# design.net
KiCad netlist of a schematic drawn in Altium Designer
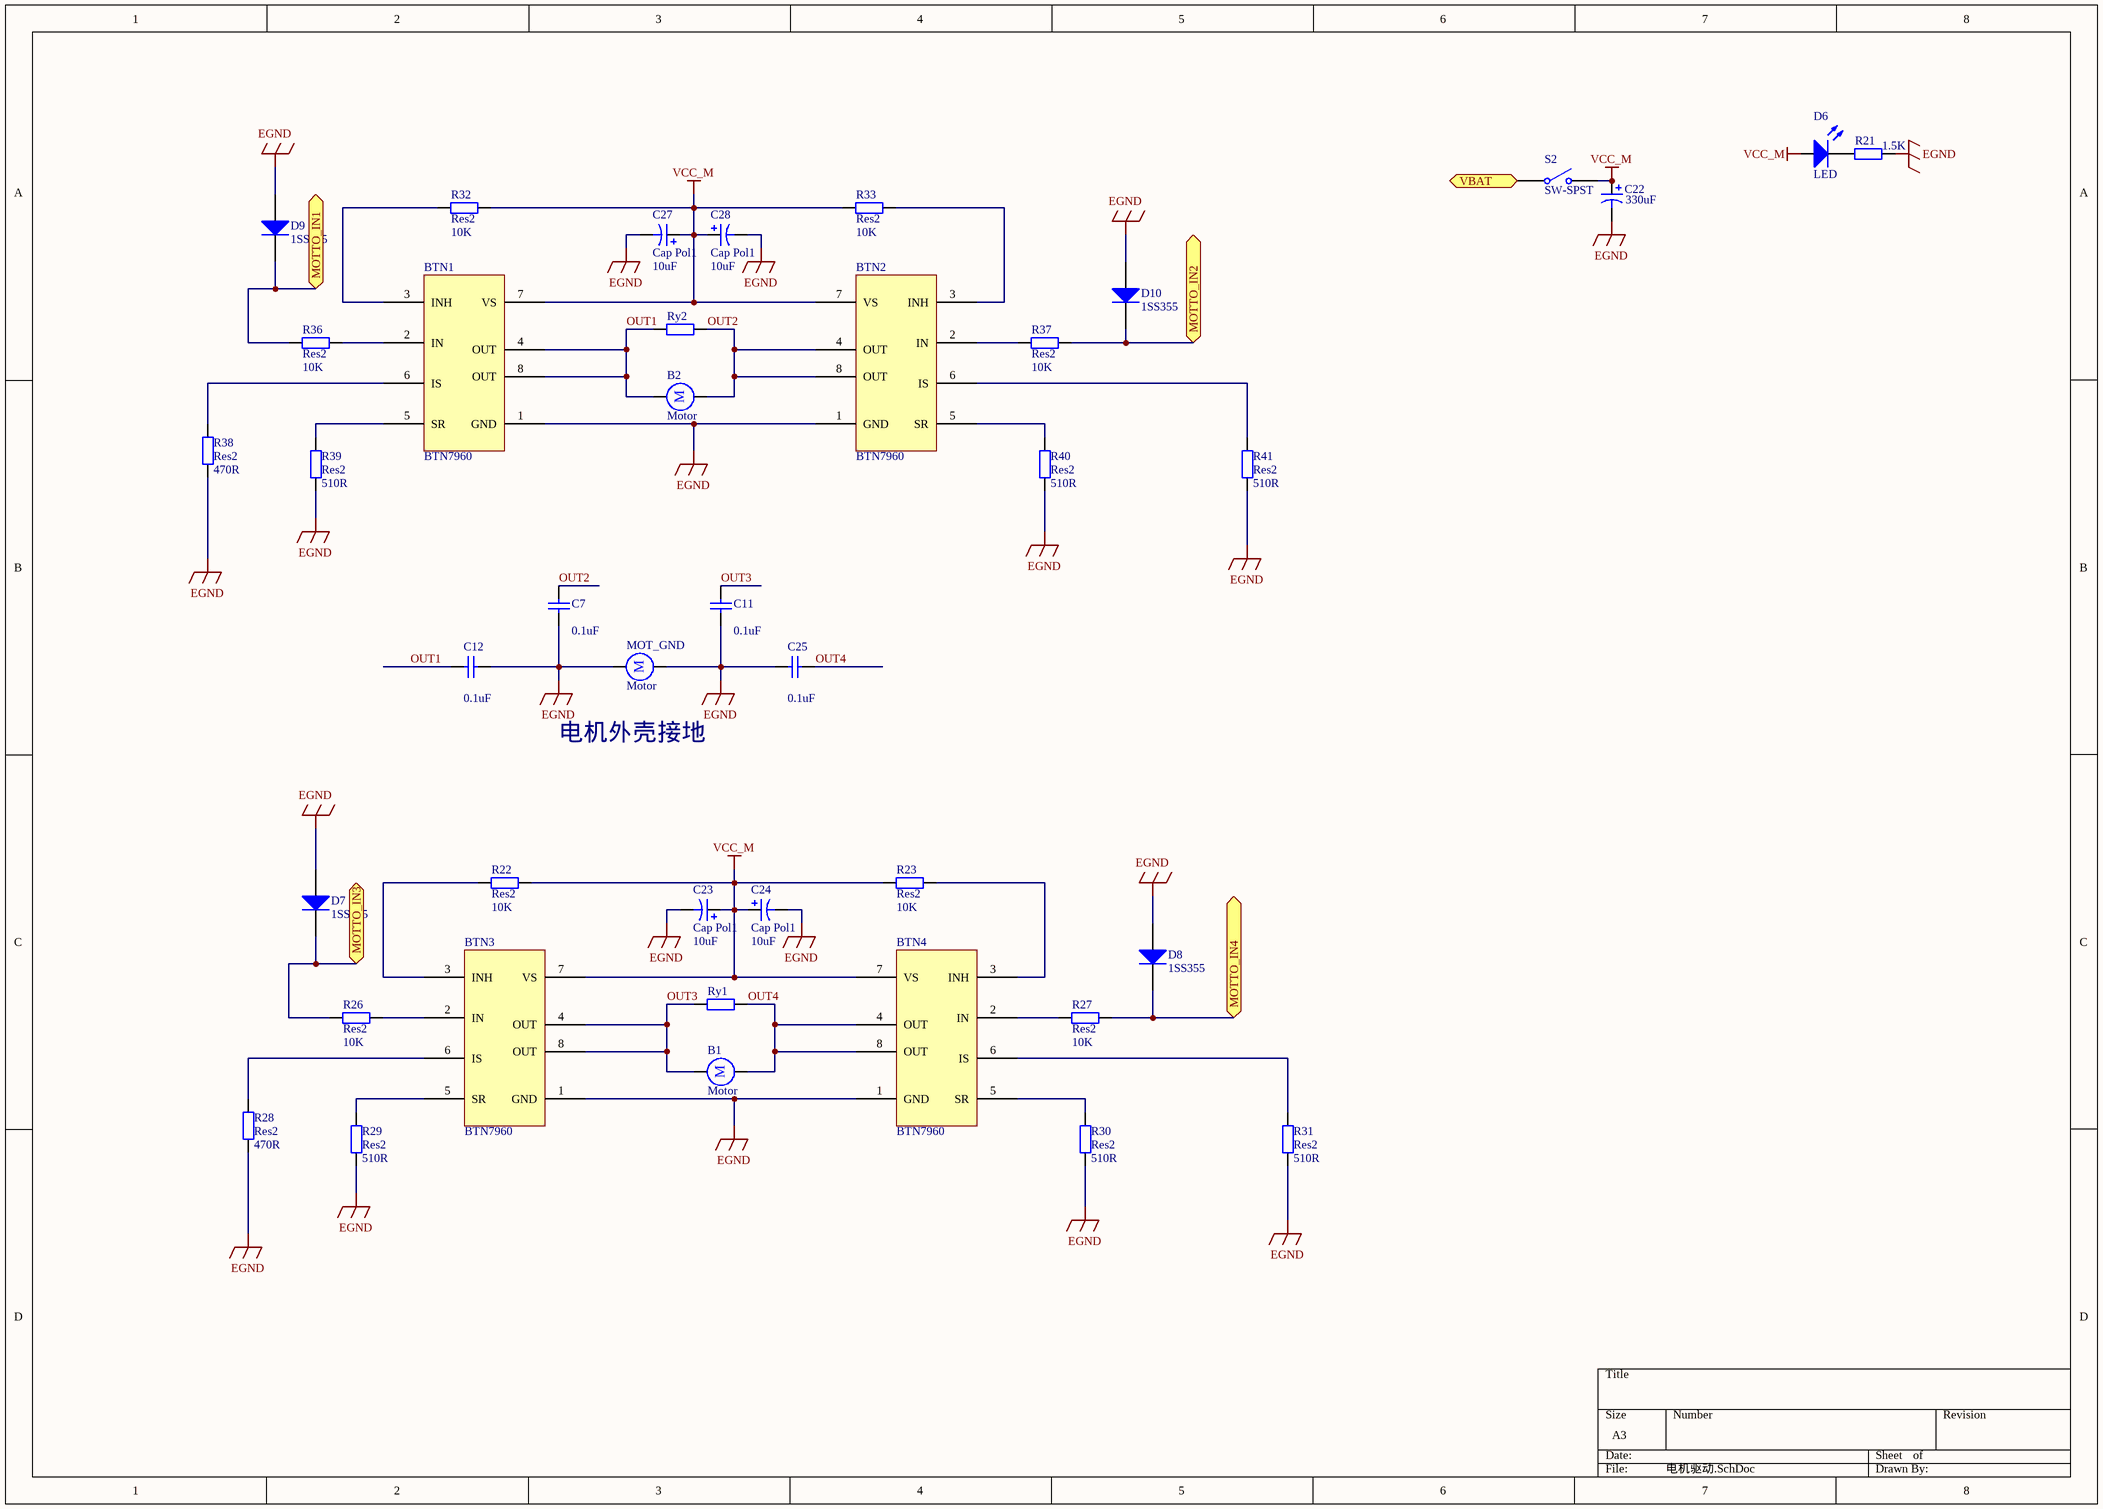
[diagram p0: 电机驱动.SchDoc]

(export (version "E")
  (design (tool "Eeschema 10.0.6"))
  (components
    (comp (ref "B1")
      (value "Motor")
      (footprint "KF301-2P")
      (description "Motor, General Kind")
      (libsource (lib "Landzo") (part "Motor"))
    )
    (comp (ref "B2")
      (value "Motor")
      (footprint "KF301-2P")
      (description "Motor, General Kind")
      (libsource (lib "Landzo") (part "Motor"))
    )
    (comp (ref "BTN1") (value "BTN7960") (footprint "PG-TO263-7-1") (libsource (lib "") (part "BTN7960_1")))
    (comp (ref "BTN2")
      (value "BTN7960")
      (footprint "PG-TO263-7-1")
      (libsource (lib "Landzo") (part "BTN7960"))
    )
    (comp (ref "BTN3") (value "BTN7960") (footprint "PG-TO263-7-1") (libsource (lib "") (part "BTN7960_1")))
    (comp (ref "BTN4")
      (value "BTN7960")
      (footprint "PG-TO263-7-1")
      (libsource (lib "Landzo") (part "BTN7960"))
    )
    (comp (ref "C7")
      (value "0.1uF")
      (footprint "C2012")
      (description "Capacitor")
      (fields (field (name "Comment") "Cap") (field (name "PUBLISHER") "Altium Limited"))
      (libsource (lib "Miscellaneous Devices") (part "Cap"))
    )
    (comp (ref "C11")
      (value "0.1uF")
      (footprint "C2012")
      (description "Capacitor")
      (fields (field (name "Comment") "Cap") (field (name "PUBLISHER") "Altium Limited"))
      (libsource (lib "Miscellaneous Devices") (part "Cap"))
    )
    (comp (ref "C12")
      (value "0.1uF")
      (footprint "C2012")
      (description "Capacitor")
      (fields (field (name "Comment") "Cap") (field (name "PUBLISHER") "Altium Limited"))
      (libsource (lib "Miscellaneous Devices") (part "Cap"))
    )
    (comp (ref "C22")
      (value "330uF")
      (footprint "SMD-EC-F8")
      (description "Polarized Capacitor (Radial)")
      (fields (field (name "Comment") "Cap Pol1") (field (name "PUBLISHER") "Altium Limited"))
      (libsource (lib "Miscellaneous Devices") (part "Cap Pol1"))
    )
    (comp (ref "C23")
      (value "Cap Pol1")
      (footprint "1206(2)")
      (description "Polarized Capacitor (Radial)")
      (fields (field (name "ALTIUM_VALUE") "10uF") (field (name "PUBLISHER") "Altium Limited"))
      (libsource (lib "Miscellaneous Devices") (part "Cap Pol1"))
    )
    (comp (ref "C24")
      (value "Cap Pol1")
      (footprint "1206(2)")
      (description "Polarized Capacitor (Radial)")
      (fields (field (name "ALTIUM_VALUE") "10uF") (field (name "PUBLISHER") "Altium Limited"))
      (libsource (lib "Miscellaneous Devices") (part "Cap Pol1"))
    )
    (comp (ref "C25")
      (value "0.1uF")
      (footprint "C2012")
      (description "Capacitor")
      (fields (field (name "Comment") "Cap") (field (name "PUBLISHER") "Altium Limited"))
      (libsource (lib "Miscellaneous Devices") (part "Cap"))
    )
    (comp (ref "C27")
      (value "Cap Pol1")
      (footprint "1206(2)")
      (description "Polarized Capacitor (Radial)")
      (fields (field (name "ALTIUM_VALUE") "10uF") (field (name "PUBLISHER") "Altium Limited"))
      (libsource (lib "Miscellaneous Devices") (part "Cap Pol1"))
    )
    (comp (ref "C28")
      (value "Cap Pol1")
      (footprint "1206(2)")
      (description "Polarized Capacitor (Radial)")
      (fields (field (name "ALTIUM_VALUE") "10uF") (field (name "PUBLISHER") "Altium Limited"))
      (libsource (lib "Miscellaneous Devices") (part "Cap Pol1"))
    )
    (comp (ref "D6")
      (value "LED")
      (footprint "C2012")
      (description "Typical INFRARED GaAs LED")
      (libsource (lib "Landzo") (part "LED"))
    )
    (comp (ref "D7")
      (value "1SS355")
      (footprint "1206(2)")
      (description "High Conductance Fast Diode")
      (fields (field (name "PUBLISHER") "Altium Limited"))
      (libsource (lib "K60-V4.0") (part "Diode 1N4148"))
    )
    (comp (ref "D8")
      (value "1SS355")
      (footprint "1206(2)")
      (description "High Conductance Fast Diode")
      (fields (field (name "PUBLISHER") "Altium Limited"))
      (libsource (lib "K60-V4.0") (part "Diode 1N4148"))
    )
    (comp (ref "D9")
      (value "1SS355")
      (footprint "1206(2)")
      (description "High Conductance Fast Diode")
      (fields (field (name "PUBLISHER") "Altium Limited"))
      (libsource (lib "K60-V4.0") (part "Diode 1N4148"))
    )
    (comp (ref "D10")
      (value "1SS355")
      (footprint "1206(2)")
      (description "High Conductance Fast Diode")
      (fields (field (name "PUBLISHER") "Altium Limited"))
      (libsource (lib "K60-V4.0") (part "Diode 1N4148"))
    )
    (comp (ref "MOT_GND")
      (value "Motor")
      (footprint "KF301-2P")
      (description "Motor, General Kind")
      (libsource (lib "Landzo") (part "Motor"))
    )
    (comp (ref "R21")
      (value "1.5K")
      (footprint "R2012")
      (description "Resistor")
      (fields (field (name "Comment") "Res2") (field (name "PUBLISHER") "Altium Limited"))
      (libsource (lib "Miscellaneous Devices") (part "Res2"))
    )
    (comp (ref "R22")
      (value "Res2")
      (footprint "R2012")
      (description "Resistor")
      (fields (field (name "ALTIUM_VALUE") "10K") (field (name "PUBLISHER") "Altium Limited"))
      (libsource (lib "") (part "Res2_1"))
    )
    (comp (ref "R23")
      (value "Res2")
      (footprint "R2012")
      (description "Resistor")
      (fields (field (name "ALTIUM_VALUE") "10K") (field (name "PUBLISHER") "Altium Limited"))
      (libsource (lib "") (part "Res2_1"))
    )
    (comp (ref "R26")
      (value "Res2")
      (footprint "R2012")
      (description "Resistor")
      (fields (field (name "ALTIUM_VALUE") "10K") (field (name "PUBLISHER") "Altium Limited"))
      (libsource (lib "") (part "Res2_1"))
    )
    (comp (ref "R27")
      (value "Res2")
      (footprint "R2012")
      (description "Resistor")
      (fields (field (name "ALTIUM_VALUE") "10K") (field (name "PUBLISHER") "Altium Limited"))
      (libsource (lib "") (part "Res2_1"))
    )
    (comp (ref "R28")
      (value "Res2")
      (footprint "R2012")
      (description "Resistor")
      (fields (field (name "ALTIUM_VALUE") "470R") (field (name "PUBLISHER") "Altium Limited"))
      (libsource (lib "") (part "Res2_2"))
    )
    (comp (ref "R29")
      (value "Res2")
      (footprint "R2012")
      (description "Resistor")
      (fields (field (name "ALTIUM_VALUE") "510R") (field (name "PUBLISHER") "Altium Limited"))
      (libsource (lib "") (part "Res2_2"))
    )
    (comp (ref "R30")
      (value "Res2")
      (footprint "R2012")
      (description "Resistor")
      (fields (field (name "ALTIUM_VALUE") "510R") (field (name "PUBLISHER") "Altium Limited"))
      (libsource (lib "") (part "Res2_2"))
    )
    (comp (ref "R31")
      (value "Res2")
      (footprint "R2012")
      (description "Resistor")
      (fields (field (name "ALTIUM_VALUE") "510R") (field (name "PUBLISHER") "Altium Limited"))
      (libsource (lib "") (part "Res2_2"))
    )
    (comp (ref "R32")
      (value "Res2")
      (footprint "R2012")
      (description "Resistor")
      (fields (field (name "ALTIUM_VALUE") "10K") (field (name "PUBLISHER") "Altium Limited"))
      (libsource (lib "") (part "Res2_1"))
    )
    (comp (ref "R33")
      (value "Res2")
      (footprint "R2012")
      (description "Resistor")
      (fields (field (name "ALTIUM_VALUE") "10K") (field (name "PUBLISHER") "Altium Limited"))
      (libsource (lib "") (part "Res2_1"))
    )
    (comp (ref "R36")
      (value "Res2")
      (footprint "R2012")
      (description "Resistor")
      (fields (field (name "ALTIUM_VALUE") "10K") (field (name "PUBLISHER") "Altium Limited"))
      (libsource (lib "") (part "Res2_1"))
    )
    (comp (ref "R37")
      (value "Res2")
      (footprint "R2012")
      (description "Resistor")
      (fields (field (name "ALTIUM_VALUE") "10K") (field (name "PUBLISHER") "Altium Limited"))
      (libsource (lib "") (part "Res2_1"))
    )
    (comp (ref "R38")
      (value "Res2")
      (footprint "R2012")
      (description "Resistor")
      (fields (field (name "ALTIUM_VALUE") "470R") (field (name "PUBLISHER") "Altium Limited"))
      (libsource (lib "") (part "Res2_2"))
    )
    (comp (ref "R39")
      (value "Res2")
      (footprint "R2012")
      (description "Resistor")
      (fields (field (name "ALTIUM_VALUE") "510R") (field (name "PUBLISHER") "Altium Limited"))
      (libsource (lib "") (part "Res2_2"))
    )
    (comp (ref "R40")
      (value "Res2")
      (footprint "R2012")
      (description "Resistor")
      (fields (field (name "ALTIUM_VALUE") "510R") (field (name "PUBLISHER") "Altium Limited"))
      (libsource (lib "") (part "Res2_2"))
    )
    (comp (ref "R41")
      (value "Res2")
      (footprint "R2012")
      (description "Resistor")
      (fields (field (name "ALTIUM_VALUE") "510R") (field (name "PUBLISHER") "Altium Limited"))
      (libsource (lib "") (part "Res2_2"))
    )
    (comp (ref "Ry1")
      (value "~")
      (footprint "1206(2)")
      (description "Resistor")
      (libsource (lib "Landzo") (part "Res"))
    )
    (comp (ref "Ry2")
      (value "~")
      (footprint "1206(2)")
      (description "Resistor")
      (libsource (lib "Landzo") (part "Res"))
    )
    (comp (ref "S2")
      (value "SW-SPST")
      (footprint "SW-125V6A(-)")
      (description "Single-Pole, Single-Throw Switch")
      (fields (field (name "PUBLISHER") "Altium Limited"))
      (libsource (lib "Miscellaneous Devices") (part "SW-SPST"))
    )
  )
  (nets
    (net (code "1") (name "/MOTTO_IN1") (class "Default")
      (node (ref "D9") (pin "2") (pinfunction "K_2") (pintype "passive"))
      (node (ref "R36") (pin "1") (pinfunction "1_1") (pintype "passive"))
    )
    (net (code "2") (name "/MOTTO_IN2") (class "Default")
      (node (ref "D10") (pin "2") (pinfunction "K_2") (pintype "passive"))
      (node (ref "R37") (pin "2") (pinfunction "2_2") (pintype "passive"))
    )
    (net (code "3") (name "/MOTTO_IN3") (class "Default")
      (node (ref "D7") (pin "2") (pinfunction "K_2") (pintype "passive"))
      (node (ref "R26") (pin "1") (pinfunction "1_1") (pintype "passive"))
    )
    (net (code "4") (name "/MOTTO_IN4") (class "Default")
      (node (ref "D8") (pin "2") (pinfunction "K_2") (pintype "passive"))
      (node (ref "R27") (pin "2") (pinfunction "2_2") (pintype "passive"))
    )
    (net (code "5") (name "/OUT1") (class "Default")
      (node (ref "B2") (pin "1") (pinfunction "1_1") (pintype "passive"))
      (node (ref "BTN1") (pin "4") (pinfunction "OUT_4") (pintype "passive"))
      (node (ref "BTN1") (pin "8") (pinfunction "OUT_8") (pintype "passive"))
      (node (ref "C12") (pin "1") (pinfunction "1_1") (pintype "passive"))
      (node (ref "Ry2") (pin "1") (pinfunction "1_1") (pintype "passive"))
    )
    (net (code "6") (name "/OUT2") (class "Default")
      (node (ref "B2") (pin "2") (pinfunction "2_2") (pintype "passive"))
      (node (ref "BTN2") (pin "4") (pinfunction "OUT_4") (pintype "passive"))
      (node (ref "BTN2") (pin "8") (pinfunction "OUT_8") (pintype "passive"))
      (node (ref "C7") (pin "1") (pinfunction "1_1") (pintype "passive"))
      (node (ref "Ry2") (pin "2") (pinfunction "2_2") (pintype "passive"))
    )
    (net (code "7") (name "/OUT3") (class "Default")
      (node (ref "B1") (pin "1") (pinfunction "1_1") (pintype "passive"))
      (node (ref "BTN3") (pin "4") (pinfunction "OUT_4") (pintype "passive"))
      (node (ref "BTN3") (pin "8") (pinfunction "OUT_8") (pintype "passive"))
      (node (ref "C11") (pin "1") (pinfunction "1_1") (pintype "passive"))
      (node (ref "Ry1") (pin "1") (pinfunction "1_1") (pintype "passive"))
    )
    (net (code "8") (name "/OUT4") (class "Default")
      (node (ref "B1") (pin "2") (pinfunction "2_2") (pintype "passive"))
      (node (ref "BTN4") (pin "4") (pinfunction "OUT_4") (pintype "passive"))
      (node (ref "BTN4") (pin "8") (pinfunction "OUT_8") (pintype "passive"))
      (node (ref "C25") (pin "2") (pinfunction "2_2") (pintype "passive"))
      (node (ref "Ry1") (pin "2") (pinfunction "2_2") (pintype "passive"))
    )
    (net (code "9") (name "/VBAT") (class "Default")
      (node (ref "S2") (pin "1") (pinfunction "COMMON_1") (pintype "passive"))
    )
    (net (code "10") (name "EGND") (class "Default")
      (node (ref "BTN1") (pin "1") (pinfunction "GND_1") (pintype "passive"))
      (node (ref "BTN2") (pin "1") (pinfunction "GND_1") (pintype "passive"))
      (node (ref "BTN3") (pin "1") (pinfunction "GND_1") (pintype "passive"))
      (node (ref "BTN4") (pin "1") (pinfunction "GND_1") (pintype "passive"))
      (node (ref "C11") (pin "2") (pinfunction "2_2") (pintype "passive"))
      (node (ref "C12") (pin "2") (pinfunction "2_2") (pintype "passive"))
      (node (ref "C22") (pin "2") (pinfunction "2_2") (pintype "passive"))
      (node (ref "C23") (pin "2") (pinfunction "2_2") (pintype "passive"))
      (node (ref "C24") (pin "2") (pinfunction "2_2") (pintype "passive"))
      (node (ref "C25") (pin "1") (pinfunction "1_1") (pintype "passive"))
      (node (ref "C27") (pin "2") (pinfunction "2_2") (pintype "passive"))
      (node (ref "C28") (pin "2") (pinfunction "2_2") (pintype "passive"))
      (node (ref "C7") (pin "2") (pinfunction "2_2") (pintype "passive"))
      (node (ref "D10") (pin "1") (pinfunction "A_1") (pintype "passive"))
      (node (ref "D7") (pin "1") (pinfunction "A_1") (pintype "passive"))
      (node (ref "D8") (pin "1") (pinfunction "A_1") (pintype "passive"))
      (node (ref "D9") (pin "1") (pinfunction "A_1") (pintype "passive"))
      (node (ref "MOT_GND") (pin "1") (pinfunction "1_1") (pintype "passive"))
      (node (ref "MOT_GND") (pin "2") (pinfunction "2_2") (pintype "passive"))
      (node (ref "R21") (pin "1") (pinfunction "1_1") (pintype "passive"))
      (node (ref "R28") (pin "1") (pinfunction "1_1") (pintype "passive"))
      (node (ref "R29") (pin "1") (pinfunction "1_1") (pintype "passive"))
      (node (ref "R30") (pin "1") (pinfunction "1_1") (pintype "passive"))
      (node (ref "R31") (pin "1") (pinfunction "1_1") (pintype "passive"))
      (node (ref "R38") (pin "1") (pinfunction "1_1") (pintype "passive"))
      (node (ref "R39") (pin "1") (pinfunction "1_1") (pintype "passive"))
      (node (ref "R40") (pin "1") (pinfunction "1_1") (pintype "passive"))
      (node (ref "R41") (pin "1") (pinfunction "1_1") (pintype "passive"))
    )
    (net (code "11") (name "Net-(BTN1-IN)") (class "Default")
      (node (ref "BTN1") (pin "2") (pinfunction "IN_2") (pintype "passive"))
      (node (ref "R36") (pin "2") (pinfunction "2_2") (pintype "passive"))
    )
    (net (code "12") (name "Net-(BTN1-INH)") (class "Default")
      (node (ref "BTN1") (pin "3") (pinfunction "INH_3") (pintype "passive"))
      (node (ref "R32") (pin "1") (pinfunction "1_1") (pintype "passive"))
    )
    (net (code "13") (name "Net-(BTN1-IS)") (class "Default")
      (node (ref "BTN1") (pin "6") (pinfunction "IS_6") (pintype "passive"))
      (node (ref "R38") (pin "2") (pinfunction "2_2") (pintype "passive"))
    )
    (net (code "14") (name "Net-(BTN1-SR)") (class "Default")
      (node (ref "BTN1") (pin "5") (pinfunction "SR_5") (pintype "passive"))
      (node (ref "R39") (pin "2") (pinfunction "2_2") (pintype "passive"))
    )
    (net (code "15") (name "Net-(BTN2-IN)") (class "Default")
      (node (ref "BTN2") (pin "2") (pinfunction "IN_2") (pintype "passive"))
      (node (ref "R37") (pin "1") (pinfunction "1_1") (pintype "passive"))
    )
    (net (code "16") (name "Net-(BTN2-INH)") (class "Default")
      (node (ref "BTN2") (pin "3") (pinfunction "INH_3") (pintype "passive"))
      (node (ref "R33") (pin "2") (pinfunction "2_2") (pintype "passive"))
    )
    (net (code "17") (name "Net-(BTN2-IS)") (class "Default")
      (node (ref "BTN2") (pin "6") (pinfunction "IS_6") (pintype "passive"))
      (node (ref "R41") (pin "2") (pinfunction "2_2") (pintype "passive"))
    )
    (net (code "18") (name "Net-(BTN2-SR)") (class "Default")
      (node (ref "BTN2") (pin "5") (pinfunction "SR_5") (pintype "passive"))
      (node (ref "R40") (pin "2") (pinfunction "2_2") (pintype "passive"))
    )
    (net (code "19") (name "Net-(BTN3-IN)") (class "Default")
      (node (ref "BTN3") (pin "2") (pinfunction "IN_2") (pintype "passive"))
      (node (ref "R26") (pin "2") (pinfunction "2_2") (pintype "passive"))
    )
    (net (code "20") (name "Net-(BTN3-INH)") (class "Default")
      (node (ref "BTN3") (pin "3") (pinfunction "INH_3") (pintype "passive"))
      (node (ref "R22") (pin "1") (pinfunction "1_1") (pintype "passive"))
    )
    (net (code "21") (name "Net-(BTN3-IS)") (class "Default")
      (node (ref "BTN3") (pin "6") (pinfunction "IS_6") (pintype "passive"))
      (node (ref "R28") (pin "2") (pinfunction "2_2") (pintype "passive"))
    )
    (net (code "22") (name "Net-(BTN3-SR)") (class "Default")
      (node (ref "BTN3") (pin "5") (pinfunction "SR_5") (pintype "passive"))
      (node (ref "R29") (pin "2") (pinfunction "2_2") (pintype "passive"))
    )
    (net (code "23") (name "Net-(BTN4-IN)") (class "Default")
      (node (ref "BTN4") (pin "2") (pinfunction "IN_2") (pintype "passive"))
      (node (ref "R27") (pin "1") (pinfunction "1_1") (pintype "passive"))
    )
    (net (code "24") (name "Net-(BTN4-INH)") (class "Default")
      (node (ref "BTN4") (pin "3") (pinfunction "INH_3") (pintype "passive"))
      (node (ref "R23") (pin "2") (pinfunction "2_2") (pintype "passive"))
    )
    (net (code "25") (name "Net-(BTN4-IS)") (class "Default")
      (node (ref "BTN4") (pin "6") (pinfunction "IS_6") (pintype "passive"))
      (node (ref "R31") (pin "2") (pinfunction "2_2") (pintype "passive"))
    )
    (net (code "26") (name "Net-(BTN4-SR)") (class "Default")
      (node (ref "BTN4") (pin "5") (pinfunction "SR_5") (pintype "passive"))
      (node (ref "R30") (pin "2") (pinfunction "2_2") (pintype "passive"))
    )
    (net (code "27") (name "Net-(D6-Pad2)") (class "Default")
      (node (ref "D6") (pin "2") (pinfunction "2_2") (pintype "passive"))
      (node (ref "R21") (pin "2") (pinfunction "2_2") (pintype "passive"))
    )
    (net (code "28") (name "VCC_M") (class "Default")
      (node (ref "BTN1") (pin "7") (pinfunction "VS_7") (pintype "passive"))
      (node (ref "BTN2") (pin "7") (pinfunction "VS_7") (pintype "passive"))
      (node (ref "BTN3") (pin "7") (pinfunction "VS_7") (pintype "passive"))
      (node (ref "BTN4") (pin "7") (pinfunction "VS_7") (pintype "passive"))
      (node (ref "C22") (pin "1") (pinfunction "1_1") (pintype "passive"))
      (node (ref "C23") (pin "1") (pinfunction "1_1") (pintype "passive"))
      (node (ref "C24") (pin "1") (pinfunction "1_1") (pintype "passive"))
      (node (ref "C27") (pin "1") (pinfunction "1_1") (pintype "passive"))
      (node (ref "C28") (pin "1") (pinfunction "1_1") (pintype "passive"))
      (node (ref "D6") (pin "1") (pinfunction "1_1") (pintype "passive"))
      (node (ref "R22") (pin "2") (pinfunction "2_2") (pintype "passive"))
      (node (ref "R23") (pin "1") (pinfunction "1_1") (pintype "passive"))
      (node (ref "R32") (pin "2") (pinfunction "2_2") (pintype "passive"))
      (node (ref "R33") (pin "1") (pinfunction "1_1") (pintype "passive"))
      (node (ref "S2") (pin "2") (pinfunction "NO_2") (pintype "passive"))
    )
  )
)
